# 06_rng.net
KiCad netlist of a schematic drawn in Altium Designer
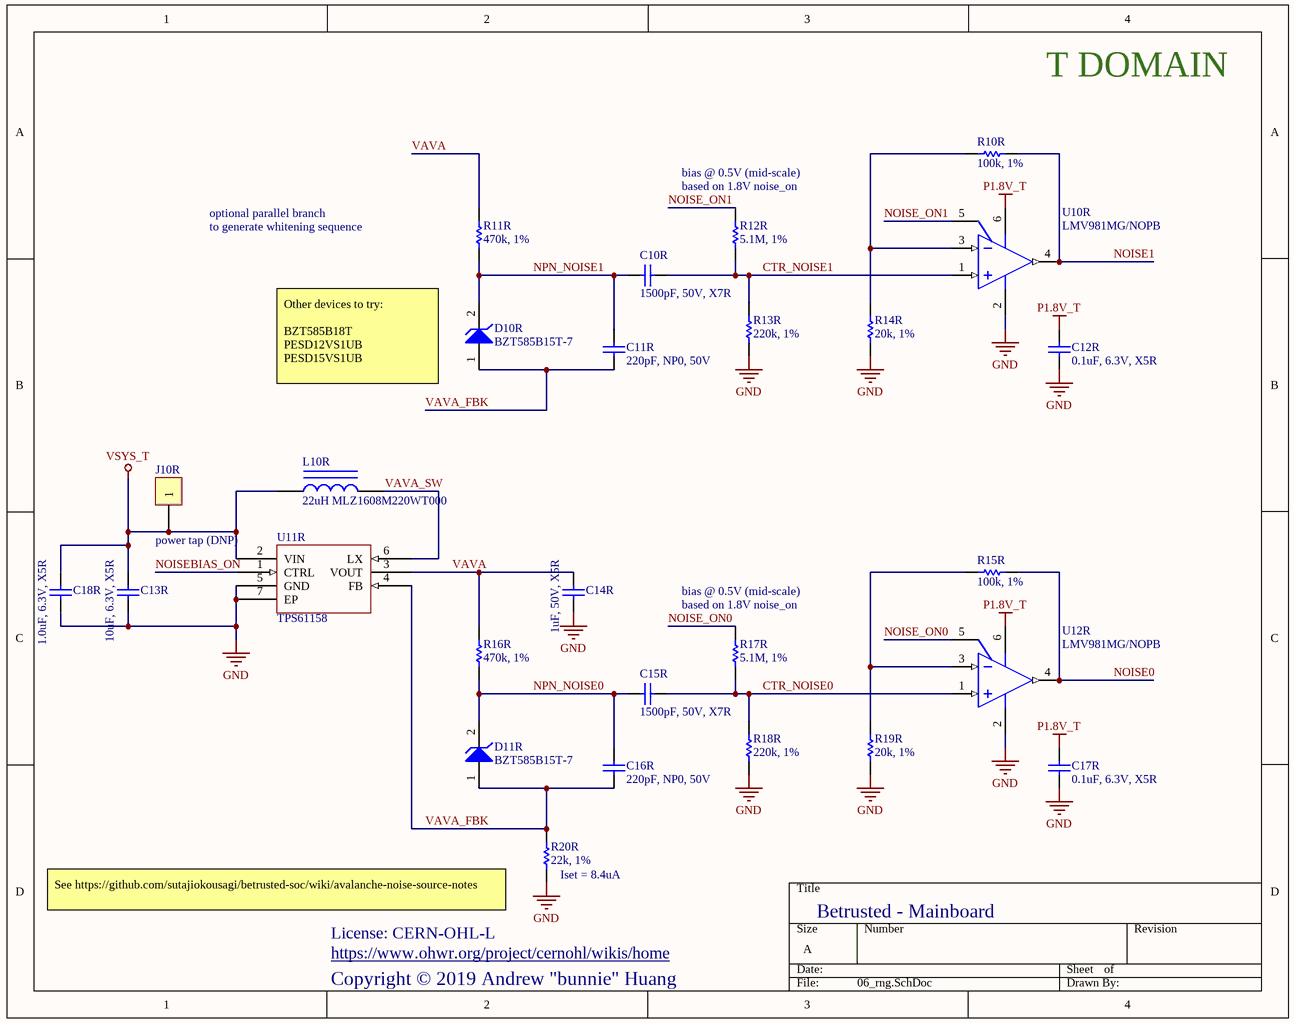
[diagram p0: 06_rng.SchDoc]

(export (version "E")
  (design (tool "Eeschema 10.0.6"))
  (components
    (comp (ref "C10R")
      (value "1500pF, 50V, X7R")
      (footprint "B_CAP0402")
      (description "Capacitor (Semiconductor SIM Model)")
      (fields (field (name "MPN") "CL05B152KB5NNNC"))
      (libsource (lib "Miscellaneous Devices") (part "Cap Semi"))
    )
    (comp (ref "C11R")
      (value "220pF, NP0, 50V")
      (footprint "B_CAP0402")
      (description "Capacitor (Semiconductor SIM Model)")
      (fields (field (name "MPN") "CL05C221JB5NNNC"))
      (libsource (lib "Miscellaneous Devices") (part "Cap Semi"))
    )
    (comp (ref "C12R")
      (value "0.1uF, 6.3V, X5R")
      (footprint "B_CAP0201")
      (description "Capacitor (Semiconductor SIM Model)")
      (fields (field (name "MPN") "CL03A104KQ3NNNC"))
      (libsource (lib "Miscellaneous Devices") (part "Cap Semi"))
    )
    (comp (ref "C13R")
      (value "10uF, 6.3V, X5R")
      (footprint "B_CAP0603")
      (description "Capacitor (Semiconductor SIM Model)")
      (fields (field (name "MPN") "CL10A106MQ8NNNC"))
      (libsource (lib "Miscellaneous Devices") (part "Cap Semi"))
    )
    (comp (ref "C14R")
      (value "1uF, 50V, X5R")
      (footprint "B_CAP0603")
      (description "Capacitor (Semiconductor SIM Model)")
      (fields (field (name "MPN") "CL10A105KB8NNNC"))
      (libsource (lib "Miscellaneous Devices") (part "Cap Semi"))
    )
    (comp (ref "C15R")
      (value "1500pF, 50V, X7R")
      (footprint "B_CAP0402")
      (description "Capacitor (Semiconductor SIM Model)")
      (fields (field (name "MPN") "CL05B152KB5NNNC"))
      (libsource (lib "Miscellaneous Devices") (part "Cap Semi"))
    )
    (comp (ref "C16R")
      (value "220pF, NP0, 50V")
      (footprint "B_CAP0402")
      (description "Capacitor (Semiconductor SIM Model)")
      (fields (field (name "MPN") "CL05C221JB5NNNC"))
      (libsource (lib "Miscellaneous Devices") (part "Cap Semi"))
    )
    (comp (ref "C17R")
      (value "0.1uF, 6.3V, X5R")
      (footprint "B_CAP0201")
      (description "Capacitor (Semiconductor SIM Model)")
      (fields (field (name "MPN") "CL03A104KQ3NNNC"))
      (libsource (lib "Miscellaneous Devices") (part "Cap Semi"))
    )
    (comp (ref "C18R")
      (value "1.0uF, 6.3V, X5R")
      (footprint "B_CAP0201")
      (description "Capacitor (Semiconductor SIM Model)")
      (fields (field (name "MPN") "GRM033R60J105MEA2D"))
      (libsource (lib "Miscellaneous Devices") (part "Cap Semi"))
    )
    (comp (ref "D10R")
      (value "BZT585B15T-7")
      (footprint "SOD523")
      (description "Zener Diode")
      (fields (field (name "PUBLISHER") "Altium Limited"))
      (libsource (lib "Miscellaneous Devices") (part "D Zener"))
    )
    (comp (ref "D11R")
      (value "BZT585B15T-7")
      (footprint "SOD523")
      (description "Zener Diode")
      (fields (field (name "PUBLISHER") "Altium Limited"))
      (libsource (lib "Miscellaneous Devices") (part "D Zener"))
    )
    (comp (ref "J10R")
      (value "power tap (DNP)")
      (footprint "RESTAP-0603")
      (description "Connector")
      (fields (field (name "MPN") "DNP"))
      (libsource (lib "*") (part "CON1"))
    )
    (comp (ref "L10R")
      (value "22uH MLZ1608M220WT000")
      (footprint "INDC1608AN")
      (description "Magnetic-Core Inductor")
      (fields (field (name "MPN") "MLZ1608M220WT000"))
      (libsource (lib "Miscellaneous Devices") (part "Inductor Iron"))
    )
    (comp (ref "R10R")
      (value "100k, 1%")
      (footprint "B_RES0201")
      (description "Resistor")
      (fields (field (name "MPN") "ANY"))
      (libsource (lib "Miscellaneous Devices") (part "Res1"))
    )
    (comp (ref "R11R")
      (value "470k, 1%")
      (footprint "B_RES0402")
      (description "Resistor")
      (fields (field (name "MPN") "ANY"))
      (libsource (lib "Miscellaneous Devices") (part "Res1"))
    )
    (comp (ref "R12R")
      (value "5.1M, 1%")
      (footprint "B_RES0402")
      (description "Resistor")
      (fields (field (name "MPN") "RMCF0402FT5M10"))
      (libsource (lib "Miscellaneous Devices") (part "Res1"))
    )
    (comp (ref "R13R")
      (value "220k, 1%")
      (footprint "B_RES0201")
      (description "Resistor")
      (fields (field (name "MPN") "ANY"))
      (libsource (lib "Miscellaneous Devices") (part "Res1"))
    )
    (comp (ref "R14R")
      (value "20k, 1%")
      (footprint "B_RES0201")
      (description "Resistor")
      (fields (field (name "MPN") "ANY"))
      (libsource (lib "Miscellaneous Devices") (part "Res1"))
    )
    (comp (ref "R15R")
      (value "100k, 1%")
      (footprint "B_RES0201")
      (description "Resistor")
      (fields (field (name "MPN") "ANY"))
      (libsource (lib "Miscellaneous Devices") (part "Res1"))
    )
    (comp (ref "R16R")
      (value "470k, 1%")
      (footprint "B_RES0402")
      (description "Resistor")
      (fields (field (name "MPN") "ANY"))
      (libsource (lib "Miscellaneous Devices") (part "Res1"))
    )
    (comp (ref "R17R")
      (value "5.1M, 1%")
      (footprint "B_RES0402")
      (description "Resistor")
      (fields (field (name "MPN") "RMCF0402FT5M10"))
      (libsource (lib "Miscellaneous Devices") (part "Res1"))
    )
    (comp (ref "R18R")
      (value "220k, 1%")
      (footprint "B_RES0201")
      (description "Resistor")
      (fields (field (name "MPN") "ANY"))
      (libsource (lib "Miscellaneous Devices") (part "Res1"))
    )
    (comp (ref "R19R")
      (value "20k, 1%")
      (footprint "B_RES0201")
      (description "Resistor")
      (fields (field (name "MPN") "ANY"))
      (libsource (lib "Miscellaneous Devices") (part "Res1"))
    )
    (comp (ref "R20R")
      (value "22k, 1%")
      (footprint "B_RES0402")
      (description "Resistor")
      (fields (field (name "MPN") "ANY"))
      (libsource (lib "Miscellaneous Devices") (part "Res1"))
    )
    (comp (ref "U10R")
      (value "LMV981MG/NOPB")
      (footprint "DCK0006A_N")
      (description "Single 1.8V, RRIO Operational Amplifiers with Shutdown, 6-pin SC-70, Pb-Free")
      (libsource (lib "Altium Content Vault") (part "AMP-OPA-LMV981-6"))
    )
    (comp (ref "U11R")
      (value "TPS61158")
      (footprint "SON65P200X80_HS-7N")
      (description "30V WLED driver with integrated power diode")
      (fields (field (name "MPN") "TPS61158DRVR"))
      (libsource (lib "commonsch-new") (part "TPS61158"))
    )
    (comp (ref "U12R")
      (value "LMV981MG/NOPB")
      (footprint "DCK0006A_N")
      (description "Single 1.8V, RRIO Operational Amplifiers with Shutdown, 6-pin SC-70, Pb-Free")
      (libsource (lib "Altium Content Vault") (part "AMP-OPA-LMV981-6"))
    )
  )
  (nets
    (net (code "1") (name "/CTR_NOISE0") (class "Default")
      (node (ref "C15R") (pin "2") (pinfunction "2_2") (pintype "passive"))
      (node (ref "R17R") (pin "1") (pinfunction "1_1") (pintype "passive"))
      (node (ref "R18R") (pin "2") (pinfunction "2_2") (pintype "passive"))
      (node (ref "U12R") (pin "1") (pinfunction "IN+_1") (pintype "input"))
    )
    (net (code "2") (name "/CTR_NOISE1") (class "Default")
      (node (ref "C10R") (pin "2") (pinfunction "2_2") (pintype "passive"))
      (node (ref "R12R") (pin "1") (pinfunction "1_1") (pintype "passive"))
      (node (ref "R13R") (pin "2") (pinfunction "2_2") (pintype "passive"))
      (node (ref "U10R") (pin "1") (pinfunction "IN+_1") (pintype "input"))
    )
    (net (code "3") (name "/NOISE0") (class "Default")
      (node (ref "R15R") (pin "1") (pinfunction "1_1") (pintype "passive"))
      (node (ref "U12R") (pin "4") (pinfunction "OUT_4") (pintype "output"))
    )
    (net (code "4") (name "/NOISE1") (class "Default")
      (node (ref "R10R") (pin "1") (pinfunction "1_1") (pintype "passive"))
      (node (ref "U10R") (pin "4") (pinfunction "OUT_4") (pintype "output"))
    )
    (net (code "5") (name "/NOISEBIAS_ON") (class "Default")
      (node (ref "U11R") (pin "1") (pinfunction "CTRL_1") (pintype "input"))
    )
    (net (code "6") (name "/NOISE_ON0") (class "Default")
      (node (ref "R17R") (pin "2") (pinfunction "2_2") (pintype "passive"))
      (node (ref "U12R") (pin "5") (pinfunction "~{SHDN}_5") (pintype "passive"))
    )
    (net (code "7") (name "/NOISE_ON1") (class "Default")
      (node (ref "R12R") (pin "2") (pinfunction "2_2") (pintype "passive"))
      (node (ref "U10R") (pin "5") (pinfunction "~{SHDN}_5") (pintype "passive"))
    )
    (net (code "8") (name "/NPN_NOISE0") (class "Default")
      (node (ref "C15R") (pin "1") (pinfunction "1_1") (pintype "passive"))
      (node (ref "C16R") (pin "2") (pinfunction "2_2") (pintype "passive"))
      (node (ref "D11R") (pin "2") (pinfunction "K_2") (pintype "passive"))
      (node (ref "R16R") (pin "1") (pinfunction "1_1") (pintype "passive"))
    )
    (net (code "9") (name "/NPN_NOISE1") (class "Default")
      (node (ref "C10R") (pin "1") (pinfunction "1_1") (pintype "passive"))
      (node (ref "C11R") (pin "2") (pinfunction "2_2") (pintype "passive"))
      (node (ref "D10R") (pin "2") (pinfunction "K_2") (pintype "passive"))
      (node (ref "R11R") (pin "1") (pinfunction "1_1") (pintype "passive"))
    )
    (net (code "10") (name "/VAVA") (class "Default")
      (node (ref "C14R") (pin "1") (pinfunction "1_1") (pintype "passive"))
      (node (ref "R11R") (pin "2") (pinfunction "2_2") (pintype "passive"))
      (node (ref "R16R") (pin "2") (pinfunction "2_2") (pintype "passive"))
      (node (ref "U11R") (pin "3") (pinfunction "VOUT_3") (pintype "power_in"))
    )
    (net (code "11") (name "/VAVA_FBK") (class "Default")
      (node (ref "C11R") (pin "1") (pinfunction "1_1") (pintype "passive"))
      (node (ref "C16R") (pin "1") (pinfunction "1_1") (pintype "passive"))
      (node (ref "D10R") (pin "1") (pinfunction "A_1") (pintype "passive"))
      (node (ref "D11R") (pin "1") (pinfunction "A_1") (pintype "passive"))
      (node (ref "R20R") (pin "2") (pinfunction "2_2") (pintype "passive"))
      (node (ref "U11R") (pin "4") (pinfunction "FB_4") (pintype "input"))
    )
    (net (code "12") (name "/VAVA_SW") (class "Default")
      (node (ref "L10R") (pin "2") (pinfunction "2_2") (pintype "passive"))
      (node (ref "U11R") (pin "6") (pinfunction "LX_6") (pintype "input"))
    )
    (net (code "13") (name "GND") (class "Default")
      (node (ref "C12R") (pin "1") (pinfunction "1_1") (pintype "passive"))
      (node (ref "C13R") (pin "2") (pinfunction "2_2") (pintype "passive"))
      (node (ref "C14R") (pin "2") (pinfunction "2_2") (pintype "passive"))
      (node (ref "C17R") (pin "1") (pinfunction "1_1") (pintype "passive"))
      (node (ref "C18R") (pin "1") (pinfunction "1_1") (pintype "passive"))
      (node (ref "R13R") (pin "1") (pinfunction "1_1") (pintype "passive"))
      (node (ref "R14R") (pin "1") (pinfunction "1_1") (pintype "passive"))
      (node (ref "R18R") (pin "1") (pinfunction "1_1") (pintype "passive"))
      (node (ref "R19R") (pin "1") (pinfunction "1_1") (pintype "passive"))
      (node (ref "R20R") (pin "1") (pinfunction "1_1") (pintype "passive"))
      (node (ref "U10R") (pin "2") (pinfunction "GND_2") (pintype "power_in"))
      (node (ref "U11R") (pin "5") (pinfunction "GND_5") (pintype "power_in"))
      (node (ref "U11R") (pin "7") (pinfunction "EP_7") (pintype "power_in"))
      (node (ref "U12R") (pin "2") (pinfunction "GND_2") (pintype "power_in"))
    )
    (net (code "14") (name "Net-(U10R-IN-)") (class "Default")
      (node (ref "R10R") (pin "2") (pinfunction "2_2") (pintype "passive"))
      (node (ref "R14R") (pin "2") (pinfunction "2_2") (pintype "passive"))
      (node (ref "U10R") (pin "3") (pinfunction "IN-_3") (pintype "input"))
    )
    (net (code "15") (name "Net-(U12R-IN-)") (class "Default")
      (node (ref "R15R") (pin "2") (pinfunction "2_2") (pintype "passive"))
      (node (ref "R19R") (pin "2") (pinfunction "2_2") (pintype "passive"))
      (node (ref "U12R") (pin "3") (pinfunction "IN-_3") (pintype "input"))
    )
    (net (code "16") (name "P1.8V_T") (class "Default")
      (node (ref "C12R") (pin "2") (pinfunction "2_2") (pintype "passive"))
      (node (ref "C17R") (pin "2") (pinfunction "2_2") (pintype "passive"))
      (node (ref "U10R") (pin "6") (pinfunction "VDD_6") (pintype "power_in"))
      (node (ref "U12R") (pin "6") (pinfunction "VDD_6") (pintype "power_in"))
    )
    (net (code "17") (name "VSYS_T") (class "Default")
      (node (ref "C13R") (pin "1") (pinfunction "1_1") (pintype "passive"))
      (node (ref "C18R") (pin "2") (pinfunction "2_2") (pintype "passive"))
      (node (ref "J10R") (pin "1") (pinfunction "1_1") (pintype "passive"))
      (node (ref "L10R") (pin "1") (pinfunction "1_1") (pintype "passive"))
      (node (ref "U11R") (pin "2") (pinfunction "VIN_2") (pintype "power_in"))
    )
  )
)
